# 7_-GSM_MODEM_MAIN.net
KiCad netlist of a schematic drawn in Altium Designer
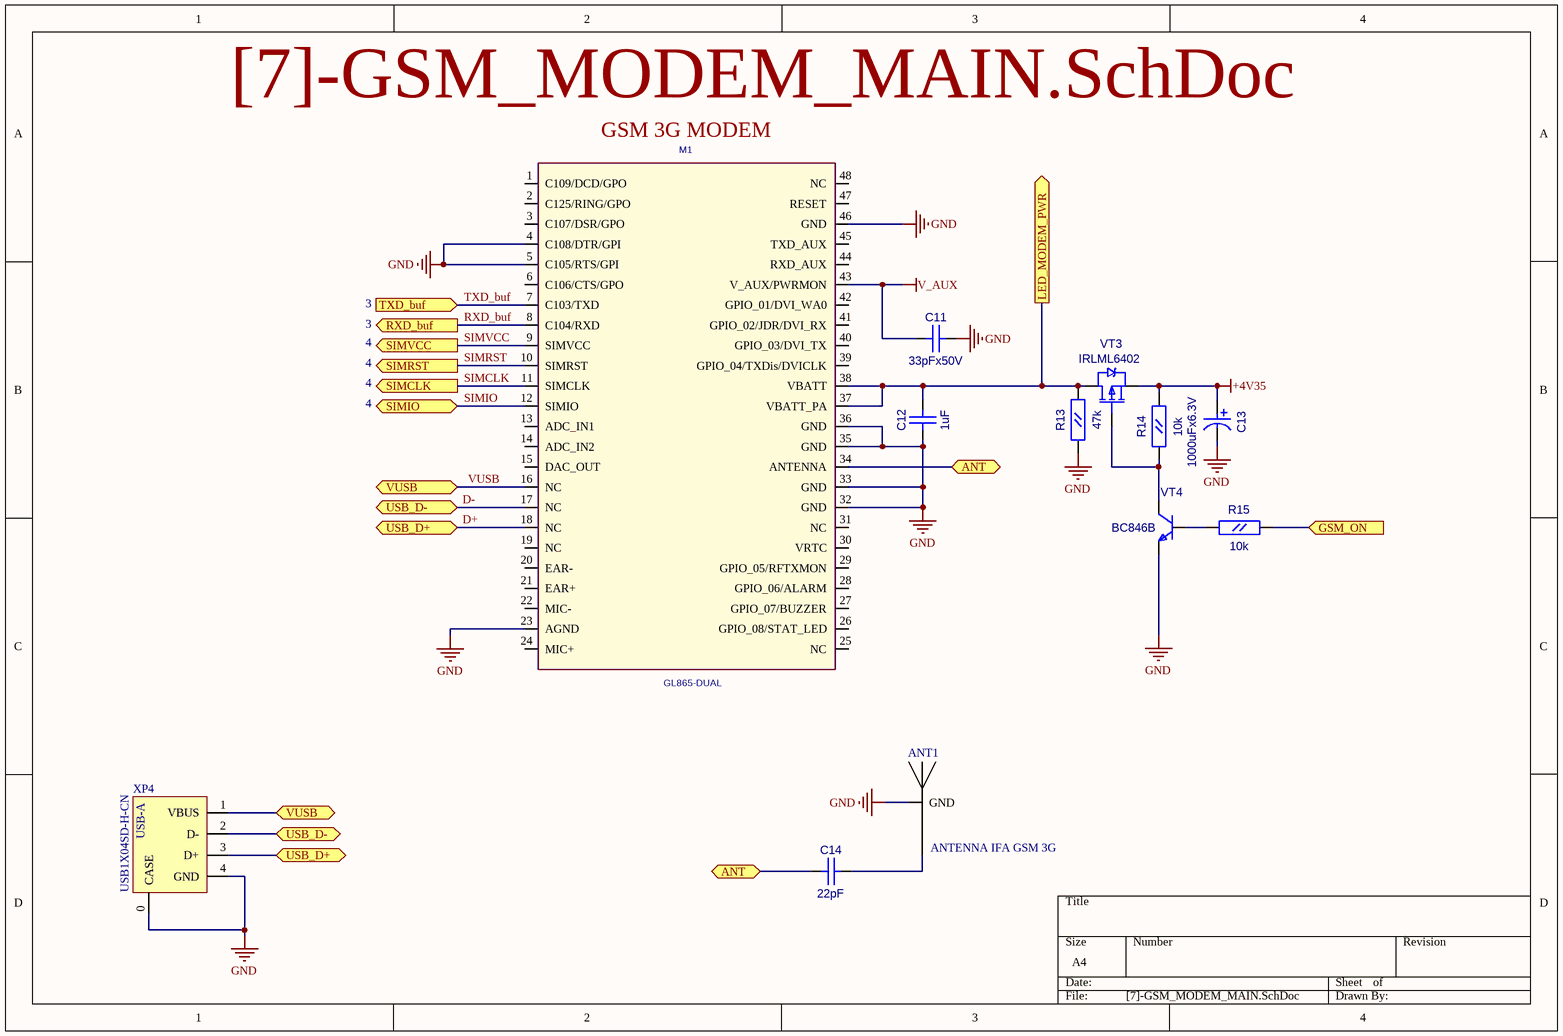
[diagram p0: [7]-GSM_MODEM_MAIN.SchDoc]

(export (version "E")
  (design (tool "Eeschema 10.0.6"))
  (components
    (comp (ref "ANT1")
      (value "ANTENNA IFA GSM 3G")
      (footprint "IFA_GSM_3G")
      (description "1.6mm Er=4.4")
      (libsource (lib "fizik_lib") (part "ANTENNA_IFA_GSM_3G"))
    )
    (comp (ref "C11")
      (value "33pFx50V")
      (footprint "CC0603")
      (description "CC0603")
      (libsource (lib "gprs_modem_2") (part "CC0603"))
    )
    (comp (ref "C12")
      (value "1uF")
      (footprint "CC0603")
      (description "CC0603")
      (libsource (lib "gprs_modem_2") (part "CC0603"))
    )
    (comp (ref "C13")
      (value "1000uFx6.3V")
      (footprint "CC8X3.5")
      (description "CAP0.35")
      (libsource (lib "fizik_lib") (part "CAP0.35"))
    )
    (comp (ref "C14")
      (value "22pF")
      (footprint "CC0603")
      (description "CC0603")
      (libsource (lib "gprs_modem_2") (part "CC0603"))
    )
    (comp (ref "M1")
      (value "GL865-DUAL")
      (footprint "GL868-DUAL")
      (description "GL868-DUAL")
      (libsource (lib "gprs_modem_2") (part "GL868-DUAL"))
    )
    (comp (ref "R13")
      (value "47k")
      (footprint "RC0603")
      (description "RC0603")
      (libsource (lib "gprs_modem_2") (part "RC0603"))
    )
    (comp (ref "R14")
      (value "10k")
      (footprint "RC0603")
      (description "RC0603")
      (libsource (lib "gprs_modem_2") (part "RC0603"))
    )
    (comp (ref "R15")
      (value "10k")
      (footprint "RC0603")
      (description "RC0603")
      (libsource (lib "gprs_modem_2") (part "RC0603"))
    )
    (comp (ref "VT3")
      (value "IRLML6402")
      (footprint "SOT-23(123)")
      (description "HEXFET Power MOSFET")
      (libsource (lib "gprs_modem_2") (part "IRLML6402"))
    )
    (comp (ref "VT4")
      (value "BC846B")
      (footprint "SOT-23(123)")
      (description "BC846BLT1")
      (libsource (lib "gprs_modem_2") (part "BC846BLT1"))
    )
    (comp (ref "XP4")
      (value "USB1X04SD-H-CN")
      (footprint "USB_A_FRONT")
      (description "Vertical USB connetctor,type A.THR")
      (libsource (lib "fizik_lib") (part "USB_A_VERTICAL"))
    )
  )
  (nets
    (net (code "1") (name "+4V35") (class "Default")
      (node (ref "C13") (pin "1") (pintype "passive"))
      (node (ref "R14") (pin "2") (pinfunction "B_2") (pintype "passive"))
      (node (ref "VT3") (pin "2") (pinfunction "S_2") (pintype "passive"))
    )
    (net (code "2") (name "/ANT") (class "Default")
      (node (ref "C14") (pin "1") (pinfunction "A_1") (pintype "passive"))
      (node (ref "M1") (pin "34") (pinfunction "ANTENNA_34") (pintype "passive"))
    )
    (net (code "3") (name "/D+") (class "Default")
      (node (ref "M1") (pin "18") (pinfunction "NC_18") (pintype "passive"))
      (node (ref "XP4") (pin "3") (pinfunction "D+_3") (pintype "passive"))
    )
    (net (code "4") (name "/D-") (class "Default")
      (node (ref "M1") (pin "17") (pinfunction "NC_17") (pintype "passive"))
      (node (ref "XP4") (pin "2") (pinfunction "D-_2") (pintype "passive"))
    )
    (net (code "5") (name "/GSM_ON") (class "Default")
      (node (ref "R15") (pin "2") (pinfunction "B_2") (pintype "passive"))
    )
    (net (code "6") (name "/LED_MODEM_PWR") (class "Default")
      (node (ref "C12") (pin "2") (pinfunction "B_2") (pintype "passive"))
      (node (ref "M1") (pin "37") (pinfunction "VBATT_PA_37") (pintype "passive"))
      (node (ref "M1") (pin "38") (pinfunction "VBATT_38") (pintype "passive"))
      (node (ref "R13") (pin "2") (pinfunction "B_2") (pintype "passive"))
      (node (ref "VT3") (pin "3") (pinfunction "D_3") (pintype "passive"))
    )
    (net (code "7") (name "/RXD_buf") (class "Default")
      (node (ref "M1") (pin "8") (pinfunction "C104/RXD_8") (pintype "passive"))
    )
    (net (code "8") (name "/SIMCLK") (class "Default")
      (node (ref "M1") (pin "11") (pinfunction "SIMCLK_11") (pintype "passive"))
    )
    (net (code "9") (name "/SIMIO") (class "Default")
      (node (ref "M1") (pin "12") (pinfunction "SIMIO_12") (pintype "passive"))
    )
    (net (code "10") (name "/SIMRST") (class "Default")
      (node (ref "M1") (pin "10") (pinfunction "SIMRST_10") (pintype "passive"))
    )
    (net (code "11") (name "/SIMVCC") (class "Default")
      (node (ref "M1") (pin "9") (pinfunction "SIMVCC_9") (pintype "passive"))
    )
    (net (code "12") (name "/TXD_buf") (class "Default")
      (node (ref "M1") (pin "7") (pinfunction "C103/TXD_7") (pintype "passive"))
    )
    (net (code "13") (name "/VUSB") (class "Default")
      (node (ref "M1") (pin "16") (pinfunction "NC_16") (pintype "passive"))
      (node (ref "XP4") (pin "1") (pinfunction "VBUS_1") (pintype "passive"))
    )
    (net (code "14") (name "GND") (class "Default")
      (node (ref "ANT1") (pin "2") (pinfunction "GND_2") (pintype "passive"))
      (node (ref "C11") (pin "2") (pinfunction "B_2") (pintype "passive"))
      (node (ref "C12") (pin "1") (pinfunction "A_1") (pintype "passive"))
      (node (ref "C13") (pin "2") (pintype "passive"))
      (node (ref "M1") (pin "23") (pinfunction "AGND_23") (pintype "passive"))
      (node (ref "M1") (pin "32") (pinfunction "GND_32") (pintype "passive"))
      (node (ref "M1") (pin "33") (pinfunction "GND_33") (pintype "passive"))
      (node (ref "M1") (pin "35") (pinfunction "GND_35") (pintype "passive"))
      (node (ref "M1") (pin "36") (pinfunction "GND_36") (pintype "passive"))
      (node (ref "M1") (pin "4") (pinfunction "C108/DTR/GPI_4") (pintype "passive"))
      (node (ref "M1") (pin "46") (pinfunction "GND_46") (pintype "passive"))
      (node (ref "M1") (pin "5") (pinfunction "C105/RTS/GPI_5") (pintype "passive"))
      (node (ref "R13") (pin "1") (pinfunction "A_1") (pintype "passive"))
      (node (ref "VT4") (pin "2") (pinfunction "E_2") (pintype "passive"))
      (node (ref "XP4") (pin "0") (pinfunction "CASE_0") (pintype "passive"))
      (node (ref "XP4") (pin "4") (pinfunction "GND_4") (pintype "passive"))
    )
    (net (code "15") (name "Net-(ANT1-RF_IN)") (class "Default")
      (node (ref "ANT1") (pin "1") (pinfunction "RF_IN_1") (pintype "passive"))
      (node (ref "C14") (pin "2") (pinfunction "B_2") (pintype "passive"))
    )
    (net (code "16") (name "Net-(R14-A)") (class "Default")
      (node (ref "R14") (pin "1") (pinfunction "A_1") (pintype "passive"))
      (node (ref "VT3") (pin "1") (pinfunction "G_1") (pintype "passive"))
      (node (ref "VT4") (pin "3") (pinfunction "C_3") (pintype "passive"))
    )
    (net (code "17") (name "Net-(R15-A)") (class "Default")
      (node (ref "R15") (pin "1") (pinfunction "A_1") (pintype "passive"))
      (node (ref "VT4") (pin "1") (pinfunction "B_1") (pintype "passive"))
    )
    (net (code "18") (name "V_AUX") (class "Default")
      (node (ref "C11") (pin "1") (pinfunction "A_1") (pintype "passive"))
      (node (ref "M1") (pin "43") (pinfunction "V_AUX/PWRMON_43") (pintype "passive"))
    )
    (net (code "19") (name "unconnected-(M1-ADC_IN1-Pad13)") (class "Default")
      (node (ref "M1") (pin "13") (pinfunction "ADC_IN1_13") (pintype "passive"))
    )
    (net (code "20") (name "unconnected-(M1-ADC_IN2-Pad14)") (class "Default")
      (node (ref "M1") (pin "14") (pinfunction "ADC_IN2_14") (pintype "passive"))
    )
    (net (code "21") (name "unconnected-(M1-C106{slash}CTS{slash}GPO-Pad6)") (class "Default")
      (node (ref "M1") (pin "6") (pinfunction "C106/CTS/GPO_6") (pintype "passive"))
    )
    (net (code "22") (name "unconnected-(M1-C107{slash}DSR{slash}GPO-Pad3)") (class "Default")
      (node (ref "M1") (pin "3") (pinfunction "C107/DSR/GPO_3") (pintype "passive"))
    )
    (net (code "23") (name "unconnected-(M1-C109{slash}DCD{slash}GPO-Pad1)") (class "Default")
      (node (ref "M1") (pin "1") (pinfunction "C109/DCD/GPO_1") (pintype "passive"))
    )
    (net (code "24") (name "unconnected-(M1-C125{slash}RING{slash}GPO-Pad2)") (class "Default")
      (node (ref "M1") (pin "2") (pinfunction "C125/RING/GPO_2") (pintype "passive"))
    )
    (net (code "25") (name "unconnected-(M1-DAC_OUT-Pad15)") (class "Default")
      (node (ref "M1") (pin "15") (pinfunction "DAC_OUT_15") (pintype "passive"))
    )
    (net (code "26") (name "unconnected-(M1-EAR+-Pad21)") (class "Default")
      (node (ref "M1") (pin "21") (pinfunction "EAR+_21") (pintype "passive"))
    )
    (net (code "27") (name "unconnected-(M1-EAR--Pad20)") (class "Default")
      (node (ref "M1") (pin "20") (pinfunction "EAR-_20") (pintype "passive"))
    )
    (net (code "28") (name "unconnected-(M1-GPIO_01{slash}DVI_WA0-Pad42)") (class "Default")
      (node (ref "M1") (pin "42") (pinfunction "GPIO_01/DVI_WA0_42") (pintype "passive"))
    )
    (net (code "29") (name "unconnected-(M1-GPIO_02{slash}JDR{slash}DVI_RX-Pad41)") (class "Default")
      (node (ref "M1") (pin "41") (pinfunction "GPIO_02/JDR/DVI_RX_41") (pintype "passive"))
    )
    (net (code "30") (name "unconnected-(M1-GPIO_03{slash}DVI_TX-Pad40)") (class "Default")
      (node (ref "M1") (pin "40") (pinfunction "GPIO_03/DVI_TX_40") (pintype "passive"))
    )
    (net (code "31") (name "unconnected-(M1-GPIO_04{slash}TXDis{slash}DVICLK-Pad39)") (class "Default")
      (node (ref "M1") (pin "39") (pinfunction "GPIO_04/TXDis/DVICLK_39") (pintype "passive"))
    )
    (net (code "32") (name "unconnected-(M1-GPIO_05{slash}RFTXMON-Pad29)") (class "Default")
      (node (ref "M1") (pin "29") (pinfunction "GPIO_05/RFTXMON_29") (pintype "passive"))
    )
    (net (code "33") (name "unconnected-(M1-GPIO_06{slash}ALARM-Pad28)") (class "Default")
      (node (ref "M1") (pin "28") (pinfunction "GPIO_06/ALARM_28") (pintype "passive"))
    )
    (net (code "34") (name "unconnected-(M1-GPIO_07{slash}BUZZER-Pad27)") (class "Default")
      (node (ref "M1") (pin "27") (pinfunction "GPIO_07/BUZZER_27") (pintype "passive"))
    )
    (net (code "35") (name "unconnected-(M1-GPIO_08{slash}STAT_LED-Pad26)") (class "Default")
      (node (ref "M1") (pin "26") (pinfunction "GPIO_08/STAT_LED_26") (pintype "passive"))
    )
    (net (code "36") (name "unconnected-(M1-MIC+-Pad24)") (class "Default")
      (node (ref "M1") (pin "24") (pinfunction "MIC+_24") (pintype "passive"))
    )
    (net (code "37") (name "unconnected-(M1-MIC--Pad22)") (class "Default")
      (node (ref "M1") (pin "22") (pinfunction "MIC-_22") (pintype "passive"))
    )
    (net (code "38") (name "unconnected-(M1-NC-Pad19)") (class "Default")
      (node (ref "M1") (pin "19") (pinfunction "NC_19") (pintype "passive"))
    )
    (net (code "39") (name "unconnected-(M1-NC-Pad25)") (class "Default")
      (node (ref "M1") (pin "25") (pinfunction "NC_25") (pintype "passive"))
    )
    (net (code "40") (name "unconnected-(M1-NC-Pad31)") (class "Default")
      (node (ref "M1") (pin "31") (pinfunction "NC_31") (pintype "passive"))
    )
    (net (code "41") (name "unconnected-(M1-NC-Pad48)") (class "Default")
      (node (ref "M1") (pin "48") (pinfunction "NC_48") (pintype "passive"))
    )
    (net (code "42") (name "unconnected-(M1-RESET-Pad47)") (class "Default")
      (node (ref "M1") (pin "47") (pinfunction "RESET_47") (pintype "passive"))
    )
    (net (code "43") (name "unconnected-(M1-RXD_AUX-Pad44)") (class "Default")
      (node (ref "M1") (pin "44") (pinfunction "RXD_AUX_44") (pintype "passive"))
    )
    (net (code "44") (name "unconnected-(M1-TXD_AUX-Pad45)") (class "Default")
      (node (ref "M1") (pin "45") (pinfunction "TXD_AUX_45") (pintype "passive"))
    )
    (net (code "45") (name "unconnected-(M1-VRTC-Pad30)") (class "Default")
      (node (ref "M1") (pin "30") (pinfunction "VRTC_30") (pintype "passive"))
    )
  )
)
